# CompressorIface.net
KiCad netlist of a schematic drawn in Altium Designer
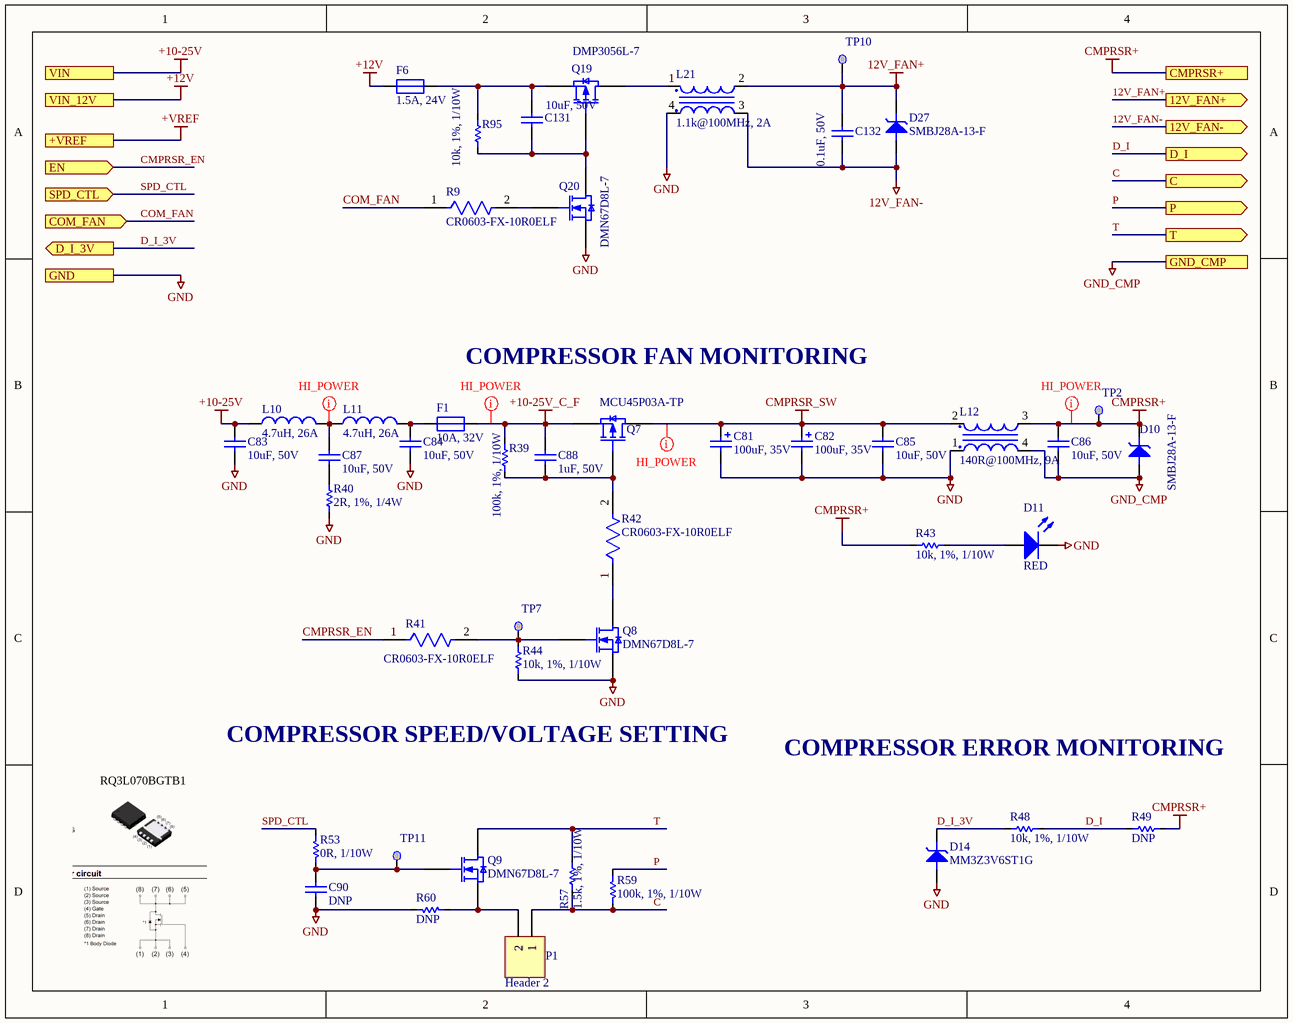
[diagram p0: CompressorIface.SchDoc]

(export (version "E")
  (design (tool "Eeschema 10.0.6"))
  (components
    (comp (ref "C81")
      (value "100uF, 35V")
      (footprint "CAPAE7866X80L")
      (description "CAP ALUM 100UF 20% 35V SMD")
      (fields (field (name "PART NUMBER") "NS00911"))
      (libsource (lib "FullPartsDB") (part "CAP_POL"))
    )
    (comp (ref "C82")
      (value "100uF, 35V")
      (footprint "CAPAE7866X80L")
      (description "CAP ALUM 100UF 20% 35V SMD")
      (fields (field (name "PART NUMBER") "NS00911"))
      (libsource (lib "FullPartsDB") (part "CAP_POL"))
    )
    (comp (ref "C83")
      (value "10uF, 50V")
      (footprint "1206")
      (description "CAP CER 10UF 50V X7R 1206")
      (fields (field (name "PART NUMBER") "NS00832"))
      (libsource (lib "FullPartsDB") (part "Cap"))
    )
    (comp (ref "C84")
      (value "10uF, 50V")
      (footprint "1206")
      (description "CAP CER 10UF 50V X7R 1206")
      (fields (field (name "PART NUMBER") "NS00832"))
      (libsource (lib "FullPartsDB") (part "Cap"))
    )
    (comp (ref "C85")
      (value "10uF, 50V")
      (footprint "1206")
      (description "CAP CER 10UF 50V X7R 1206")
      (fields (field (name "PART NUMBER") "NS00832"))
      (libsource (lib "FullPartsDB") (part "Cap"))
    )
    (comp (ref "C86")
      (value "10uF, 50V")
      (footprint "1206")
      (description "CAP CER 10UF 50V X7R 1206")
      (fields (field (name "PART NUMBER") "NS00832"))
      (libsource (lib "FullPartsDB") (part "Cap"))
    )
    (comp (ref "C87")
      (value "10uF, 50V")
      (footprint "1206")
      (description "CAP CER 10UF 50V X7R 1206")
      (fields (field (name "PART NUMBER") "NS00832"))
      (libsource (lib "FullPartsDB") (part "Cap"))
    )
    (comp (ref "C88")
      (value "1uF, 50V")
      (footprint "0805")
      (description "CAP CER 1UF 50V X7R 0805")
      (fields (field (name "PART NUMBER") "NS00871"))
      (libsource (lib "FullPartsDB") (part "Cap"))
    )
    (comp (ref "C90")
      (value "DNP")
      (footprint "0805")
      (description "0.10µF ±10% 50V Ceramic Capacitor X7R 0805 (2012 Metric)")
      (fields (field (name "PART NUMBER") "NS00353"))
      (libsource (lib "FullPartsDB") (part "Cap"))
    )
    (comp (ref "C131")
      (value "10uF, 50V")
      (footprint "1206")
      (description "CAP CER 10UF 50V X7R 1206")
      (fields (field (name "PART NUMBER") "NS00832"))
      (libsource (lib "FullPartsDB") (part "Cap"))
    )
    (comp (ref "C132")
      (value "0.1uF, 50V")
      (footprint "0603")
      (description "CAP CER 0.1UF 50V X7R 0603")
      (fields (field (name "PART NUMBER") "NS00838"))
      (libsource (lib "FullPartsDB") (part "Cap"))
    )
    (comp (ref "D10")
      (value "SMBJ28A-13-F")
      (footprint "SMB")
      (description "TVS DIODE 28VWM 45.4VC SMB")
      (fields (field (name "PART NUMBER") "NS00891"))
      (libsource (lib "FullPartsDB") (part "DiodeZener"))
    )
    (comp (ref "D11")
      (value "RED")
      (footprint "0603_DIODE_K1A2")
      (description "LED RED CLEAR 1608 SMD")
      (fields (field (name "PART NUMBER") "NS00945"))
      (libsource (lib "FullPartsDB") (part "LED_K1A2"))
    )
    (comp (ref "D14")
      (value "MM3Z3V6ST1G")
      (footprint "SOD323")
      (description "DIODE ZENER 3V 300MW SOD323")
      (fields (field (name "PART NUMBER") "NS00914"))
      (libsource (lib "FullPartsDB") (part "DiodeZener"))
    )
    (comp (ref "D27")
      (value "SMBJ28A-13-F")
      (footprint "SMB")
      (description "TVS DIODE 28VWM 45.4VC SMB")
      (fields (field (name "PART NUMBER") "NS00891"))
      (libsource (lib "FullPartsDB") (part "DiodeZener"))
    )
    (comp (ref "F1")
      (value "10A, 32V")
      (footprint "RAD_TH_1.3DIAx10.2Px27.9H")
      (description "PTC RESET FUSE 32V 10A RADIAL")
      (fields (field (name "PART NUMBER") "NS00921"))
      (libsource (lib "FullPartsDB") (part "Fuse"))
    )
    (comp (ref "F6")
      (value "1.5A, 24V")
      (footprint "1812_CAP")
      (description "PTC RESET FUSE 24V 1.5A 1812")
      (fields (field (name "PART NUMBER") "NS00950"))
      (libsource (lib "FullPartsDB") (part "Fuse"))
    )
    (comp (ref "L10")
      (value "4.7uH, 26A")
      (footprint "INDM178169X70N")
      (description "FIXED IND 4.7UH 26A 5.5 MOHM SMD")
      (fields (field (name "PART NUMBER") "NS00854"))
      (libsource (lib "FullPartsDB") (part "Inductor"))
    )
    (comp (ref "L11")
      (value "4.7uH, 26A")
      (footprint "INDM178169X70N")
      (description "FIXED IND 4.7UH 26A 5.5 MOHM SMD")
      (fields (field (name "PART NUMBER") "NS00854"))
      (libsource (lib "FullPartsDB") (part "Inductor"))
    )
    (comp (ref "L12")
      (value "140R@100MHz, 9A")
      (footprint "CHOKE_SMD_7.0X6.0X3.8")
      (description "CMC 1.8UH 9A 2LN 140 OHM SMD553-4125-1-ND")
      (fields (field (name "PART NUMBER") "NS00944"))
      (libsource (lib "FullPartsDB") (part "CHOKE_COMMON_ALT"))
    )
    (comp (ref "L21")
      (value "1.1k@100MHz, 2A")
      (footprint "PLCC440P435X370X235-4L")
      (description "CMC 2A 2LN 1.1K OHM SMD")
      (fields (field (name "PART NUMBER") "NS00952"))
      (libsource (lib "Schlib1") (part "CHOKE_COMMON_ALT"))
    )
    (comp (ref "P1")
      (value "Header 2")
      (footprint "HDR1X2")
      (description "Header, 2-Pin")
      (fields (field (name "PUBLISHER") "Altium Limited"))
      (libsource (lib "Miscellaneous Connectors") (part "Header 2"))
    )
    (comp (ref "Q7")
      (value "MCU45P03A-TP")
      (footprint "DPAK")
      (description "P-CHANNEL MOSFET, DPAK")
      (fields (field (name "PART NUMBER") "NS00810"))
      (libsource (lib "FullPartsDB") (part "FET_P_GDS"))
    )
    (comp (ref "Q8")
      (value "DMN67D8L-7")
      (footprint "SOT23-3")
      (description "MOSFET N-CH 60V 210MA SOT23")
      (fields (field (name "PART NUMBER") "NS00873") (field (name "PUBLISHER") "Altium Limited"))
      (libsource (lib "FullPartsDB") (part "FET_N_GSD"))
    )
    (comp (ref "Q9")
      (value "DMN67D8L-7")
      (footprint "SOT23-3")
      (description "MOSFET N-CH 60V 210MA SOT23")
      (fields (field (name "PART NUMBER") "NS00873") (field (name "PUBLISHER") "Altium Limited"))
      (libsource (lib "FullPartsDB") (part "FET_N_GSD"))
    )
    (comp (ref "Q19")
      (value "DMP3056L-7")
      (footprint "SOT23-3")
      (description "MOSFET P-CH 30V 4.3A SOT23")
      (fields (field (name "PART NUMBER") "NS00910"))
      (libsource (lib "FullPartsDB") (part "FET_P_GSD"))
    )
    (comp (ref "Q20")
      (value "DMN67D8L-7")
      (footprint "SOT23-3")
      (description "MOSFET N-CH 60V 210MA SOT23")
      (fields (field (name "PART NUMBER") "NS00873") (field (name "PUBLISHER") "Altium Limited"))
      (libsource (lib "FullPartsDB") (part "FET_N_GSD"))
    )
    (comp (ref "R9")
      (value "CR0603-FX-10R0ELF")
      (footprint "FP-CR0603-MFG")
      (description "Thick Film Chip Resistors 0603 10Ω 0.1W 1% 100ppm/°C")
      (fields (field (name "TOLERANCE") "1%"))
      (libsource (lib "Altium Content Vault") (part "1029c3af85768c4190bb7ad29bc67b5"))
    )
    (comp (ref "R39")
      (value "100k, 1%, 1/10W")
      (footprint "0603")
      (description "RES 100K OHM 1% 1/10W 0603")
      (fields (field (name "PART NUMBER") "NS00835"))
      (libsource (lib "FullPartsDB") (part "RESISTOR"))
    )
    (comp (ref "R40")
      (value "2R, 1%, 1/4W")
      (footprint "1206")
      (description "RES 2 OHM 1% 1/4W 1206")
      (fields (field (name "PART NUMBER") "NS00946"))
      (libsource (lib "FullPartsDB") (part "RESISTOR"))
    )
    (comp (ref "R41")
      (value "CR0603-FX-10R0ELF")
      (footprint "FP-CR0603-MFG")
      (description "Thick Film Chip Resistors 0603 10Ω 0.1W 1% 100ppm/°C")
      (fields (field (name "TOLERANCE") "1%"))
      (libsource (lib "Altium Content Vault") (part "1029c3af85768c4190bb7ad29bc67b5"))
    )
    (comp (ref "R42")
      (value "CR0603-FX-10R0ELF")
      (footprint "FP-CR0603-MFG")
      (description "Thick Film Chip Resistors 0603 10Ω 0.1W 1% 100ppm/°C")
      (fields (field (name "TOLERANCE") "1%"))
      (libsource (lib "Altium Content Vault") (part "1029c3af85768c4190bb7ad29bc67b5"))
    )
    (comp (ref "R43")
      (value "10k, 1%, 1/10W")
      (footprint "0603")
      (description "RES 10K OHM 1% 1/10W 0603")
      (fields (field (name "PART NUMBER") "NS00820"))
      (libsource (lib "FullPartsDB") (part "RESISTOR"))
    )
    (comp (ref "R44")
      (value "10k, 1%, 1/10W")
      (footprint "0603")
      (description "RES 10K OHM 1% 1/10W 0603")
      (fields (field (name "PART NUMBER") "NS00820"))
      (libsource (lib "FullPartsDB") (part "RESISTOR"))
    )
    (comp (ref "R48")
      (value "10k, 1%, 1/10W")
      (footprint "0603")
      (description "RES 10K OHM 1% 1/10W 0603")
      (fields (field (name "PART NUMBER") "NS00820"))
      (libsource (lib "FullPartsDB") (part "RESISTOR"))
    )
    (comp (ref "R49")
      (value "DNP")
      (footprint "0603")
      (description "RES 10K OHM 1% 1/10W 0603")
      (fields (field (name "PART NUMBER") "NS00820"))
      (libsource (lib "FullPartsDB") (part "RESISTOR"))
    )
    (comp (ref "R53")
      (value "0R, 1/10W")
      (footprint "0603")
      (description "RES 0 OHM JUMPER 1/10W 0603")
      (fields (field (name "PART NUMBER") "NS00876"))
      (libsource (lib "FullPartsDB") (part "RESISTOR"))
    )
    (comp (ref "R57")
      (value "1.5k, 1%, 1/10W")
      (footprint "0603")
      (description "RES 1.5K OHM 1% 1/10W 0603")
      (fields (field (name "PART NUMBER") "NS00951"))
      (libsource (lib "FullPartsDB") (part "RESISTOR"))
    )
    (comp (ref "R59")
      (value "100k, 1%, 1/10W")
      (footprint "0603")
      (description "RES SMD 100K OHM 1% 1/10W 0603")
      (fields (field (name "PART NUMBER") "NS00915"))
      (libsource (lib "FullPartsDB") (part "RESISTOR"))
    )
    (comp (ref "R60")
      (value "DNP")
      (footprint "0603")
      (description "RES 300kOHM JUMPER 1/10W 0603")
      (fields (field (name "PART NUMBER") "NS00876"))
      (libsource (lib "FullPartsDB") (part "RESISTOR"))
    )
    (comp (ref "R95")
      (value "10k, 1%, 1/10W")
      (footprint "0603")
      (description "RES 10K OHM 1% 1/10W 0603")
      (fields (field (name "PART NUMBER") "NS00820"))
      (libsource (lib "FullPartsDB") (part "RESISTOR"))
    )
    (comp (ref "TP2")
      (value "Test Point")
      (footprint "TEST POINT 40 Mil")
      (description "Test Point 0.3mm")
      (libsource (lib "1_EverythingElse") (part "Test Point"))
    )
    (comp (ref "TP7")
      (value "Test Point")
      (footprint "TEST POINT 40 Mil")
      (description "Test Point 0.3mm")
      (libsource (lib "1_EverythingElse") (part "Test Point"))
    )
    (comp (ref "TP10")
      (value "Test Point")
      (footprint "TEST POINT 40 Mil")
      (description "Test Point 0.3mm")
      (libsource (lib "1_EverythingElse") (part "Test Point"))
    )
    (comp (ref "TP11")
      (value "Test Point")
      (footprint "TEST POINT 40 Mil")
      (description "Test Point 0.3mm")
      (libsource (lib "1_EverythingElse") (part "Test Point"))
    )
  )
  (nets
    (net (code "1") (name "+10-25V") (class "Default")
      (node (ref "C83") (pin "2") (pinfunction "2_2") (pintype "passive"))
      (node (ref "L10") (pin "1") (pinfunction "1_1") (pintype "passive"))
    )
    (net (code "2") (name "+10-25V_C_F") (class "Default")
      (node (ref "C88") (pin "2") (pinfunction "2_2") (pintype "passive"))
      (node (ref "F1") (pin "1") (pinfunction "A_1") (pintype "passive"))
      (node (ref "Q7") (pin "3") (pinfunction "S_3") (pintype "passive"))
      (node (ref "R39") (pin "2") (pinfunction "2_2") (pintype "passive"))
    )
    (net (code "3") (name "+12V") (class "Default")
      (node (ref "F6") (pin "2") (pinfunction "K_2") (pintype "passive"))
    )
    (net (code "5") (name "/C") (class "Default")
      (node (ref "P1") (pin "1") (pinfunction "1_1") (pintype "passive"))
      (node (ref "R57") (pin "1") (pinfunction "1_1") (pintype "passive"))
      (node (ref "R59") (pin "2") (pinfunction "2_2") (pintype "passive"))
    )
    (net (code "6") (name "/CMPRSR_EN") (class "Default")
      (node (ref "R41") (pin "1") (pinfunction "1_1") (pintype "passive"))
    )
    (net (code "7") (name "/COM_FAN") (class "Default")
      (node (ref "R9") (pin "1") (pinfunction "1_1") (pintype "passive"))
    )
    (net (code "8") (name "/D_I") (class "Default")
      (node (ref "R48") (pin "1") (pinfunction "1_1") (pintype "passive"))
      (node (ref "R49") (pin "2") (pinfunction "2_2") (pintype "passive"))
    )
    (net (code "9") (name "/D_I_3V") (class "Default")
      (node (ref "D14") (pin "2") (pinfunction "K_2") (pintype "passive"))
      (node (ref "R48") (pin "2") (pinfunction "2_2") (pintype "passive"))
    )
    (net (code "10") (name "/P") (class "Default")
      (node (ref "R59") (pin "1") (pinfunction "1_1") (pintype "passive"))
    )
    (net (code "11") (name "/SPD_CTL") (class "Default")
      (node (ref "R53") (pin "1") (pinfunction "1_1") (pintype "passive"))
    )
    (net (code "12") (name "/T") (class "Default")
      (node (ref "Q9") (pin "3") (pinfunction "D_3") (pintype "passive"))
      (node (ref "R57") (pin "2") (pinfunction "2_2") (pintype "passive"))
    )
    (net (code "13") (name "12V_FAN+") (class "Default")
      (node (ref "C132") (pin "2") (pinfunction "2_2") (pintype "passive"))
      (node (ref "D27") (pin "2") (pinfunction "K_2") (pintype "passive"))
      (node (ref "L21") (pin "2") (pinfunction "2_2") (pintype "passive"))
      (node (ref "TP10") (pin "1") (pinfunction "1_1") (pintype "passive"))
    )
    (net (code "14") (name "12V_FAN-") (class "Default")
      (node (ref "C132") (pin "1") (pinfunction "1_1") (pintype "passive"))
      (node (ref "D27") (pin "1") (pinfunction "A_1") (pintype "passive"))
      (node (ref "L21") (pin "3") (pinfunction "3_3") (pintype "passive"))
    )
    (net (code "15") (name "CMPRSR+") (class "Default")
      (node (ref "C86") (pin "2") (pinfunction "2_2") (pintype "passive"))
      (node (ref "D10") (pin "2") (pinfunction "K_2") (pintype "passive"))
      (node (ref "L12") (pin "3") (pinfunction "3_3") (pintype "passive"))
      (node (ref "R43") (pin "2") (pinfunction "2_2") (pintype "passive"))
      (node (ref "R49") (pin "1") (pinfunction "1_1") (pintype "passive"))
      (node (ref "TP2") (pin "1") (pinfunction "1_1") (pintype "passive"))
    )
    (net (code "16") (name "CMPRSR_SW") (class "Default")
      (node (ref "C81") (pin "1") (pinfunction "1_1") (pintype "passive"))
      (node (ref "C82") (pin "1") (pinfunction "1_1") (pintype "passive"))
      (node (ref "C85") (pin "2") (pinfunction "2_2") (pintype "passive"))
      (node (ref "L12") (pin "2") (pinfunction "2_2") (pintype "passive"))
      (node (ref "Q7") (pin "2") (pinfunction "D_2") (pintype "passive"))
    )
    (net (code "17") (name "GND") (class "Default")
      (node (ref "C81") (pin "2") (pinfunction "2_2") (pintype "passive"))
      (node (ref "C82") (pin "2") (pinfunction "2_2") (pintype "passive"))
      (node (ref "C83") (pin "1") (pinfunction "1_1") (pintype "passive"))
      (node (ref "C84") (pin "1") (pinfunction "1_1") (pintype "passive"))
      (node (ref "C85") (pin "1") (pinfunction "1_1") (pintype "passive"))
      (node (ref "C90") (pin "1") (pinfunction "1_1") (pintype "passive"))
      (node (ref "D11") (pin "2") (pinfunction "K_2") (pintype "passive"))
      (node (ref "D14") (pin "1") (pinfunction "A_1") (pintype "passive"))
      (node (ref "L12") (pin "1") (pinfunction "1_1") (pintype "passive"))
      (node (ref "L21") (pin "4") (pinfunction "4_4") (pintype "passive"))
      (node (ref "Q20") (pin "2") (pinfunction "S_2") (pintype "passive"))
      (node (ref "Q8") (pin "2") (pinfunction "S_2") (pintype "passive"))
      (node (ref "R40") (pin "1") (pinfunction "1_1") (pintype "passive"))
      (node (ref "R44") (pin "1") (pinfunction "1_1") (pintype "passive"))
      (node (ref "R60") (pin "1") (pinfunction "1_1") (pintype "passive"))
    )
    (net (code "18") (name "GND_CMP") (class "Default")
      (node (ref "C86") (pin "1") (pinfunction "1_1") (pintype "passive"))
      (node (ref "D10") (pin "1") (pinfunction "A_1") (pintype "passive"))
      (node (ref "L12") (pin "4") (pinfunction "4_4") (pintype "passive"))
    )
    (net (code "19") (name "Net-(C87-Pad1)") (class "Default")
      (node (ref "C87") (pin "1") (pinfunction "1_1") (pintype "passive"))
      (node (ref "R40") (pin "2") (pinfunction "2_2") (pintype "passive"))
    )
    (net (code "20") (name "Net-(C87-Pad2)") (class "Default")
      (node (ref "C87") (pin "2") (pinfunction "2_2") (pintype "passive"))
      (node (ref "L10") (pin "2") (pinfunction "2_2") (pintype "passive"))
      (node (ref "L11") (pin "1") (pinfunction "1_1") (pintype "passive"))
    )
    (net (code "21") (name "Net-(D11-A)") (class "Default")
      (node (ref "D11") (pin "1") (pinfunction "A_1") (pintype "passive"))
      (node (ref "R43") (pin "1") (pinfunction "1_1") (pintype "passive"))
    )
    (net (code "22") (name "Net-(F1-K)") (class "Default")
      (node (ref "C84") (pin "2") (pinfunction "2_2") (pintype "passive"))
      (node (ref "F1") (pin "2") (pinfunction "K_2") (pintype "passive"))
      (node (ref "L11") (pin "2") (pinfunction "2_2") (pintype "passive"))
    )
    (net (code "23") (name "Net-(F6-A)") (class "Default")
      (node (ref "C131") (pin "1") (pinfunction "1_1") (pintype "passive"))
      (node (ref "F6") (pin "1") (pinfunction "A_1") (pintype "passive"))
      (node (ref "Q19") (pin "2") (pinfunction "S_2") (pintype "passive"))
      (node (ref "R95") (pin "1") (pinfunction "1_1") (pintype "passive"))
    )
    (net (code "24") (name "Net-(Q7-G)") (class "Default")
      (node (ref "C88") (pin "1") (pinfunction "1_1") (pintype "passive"))
      (node (ref "Q7") (pin "1") (pinfunction "G_1") (pintype "passive"))
      (node (ref "R39") (pin "1") (pinfunction "1_1") (pintype "passive"))
      (node (ref "R42") (pin "2") (pinfunction "2_2") (pintype "passive"))
    )
    (net (code "25") (name "Net-(Q8-D)") (class "Default")
      (node (ref "Q8") (pin "3") (pinfunction "D_3") (pintype "passive"))
      (node (ref "R42") (pin "1") (pinfunction "1_1") (pintype "passive"))
    )
    (net (code "26") (name "Net-(Q8-G)") (class "Default")
      (node (ref "Q8") (pin "1") (pinfunction "G_1") (pintype "passive"))
      (node (ref "R41") (pin "2") (pinfunction "2_2") (pintype "passive"))
      (node (ref "R44") (pin "2") (pinfunction "2_2") (pintype "passive"))
      (node (ref "TP7") (pin "1") (pinfunction "1_1") (pintype "passive"))
    )
    (net (code "27") (name "Net-(Q9-G)") (class "Default")
      (node (ref "C90") (pin "2") (pinfunction "2_2") (pintype "passive"))
      (node (ref "Q9") (pin "1") (pinfunction "G_1") (pintype "passive"))
      (node (ref "R53") (pin "2") (pinfunction "2_2") (pintype "passive"))
      (node (ref "TP11") (pin "1") (pinfunction "1_1") (pintype "passive"))
    )
    (net (code "28") (name "Net-(Q9-S)") (class "Default")
      (node (ref "P1") (pin "2") (pinfunction "2_2") (pintype "passive"))
      (node (ref "Q9") (pin "2") (pinfunction "S_2") (pintype "passive"))
      (node (ref "R60") (pin "2") (pinfunction "2_2") (pintype "passive"))
    )
    (net (code "29") (name "Net-(Q19-D)") (class "Default")
      (node (ref "L21") (pin "1") (pinfunction "1_1") (pintype "passive"))
      (node (ref "Q19") (pin "3") (pinfunction "D_3") (pintype "passive"))
    )
    (net (code "30") (name "Net-(Q19-G)") (class "Default")
      (node (ref "C131") (pin "2") (pinfunction "2_2") (pintype "passive"))
      (node (ref "Q19") (pin "1") (pinfunction "G_1") (pintype "passive"))
      (node (ref "Q20") (pin "3") (pinfunction "D_3") (pintype "passive"))
      (node (ref "R95") (pin "2") (pinfunction "2_2") (pintype "passive"))
    )
    (net (code "31") (name "Net-(Q20-G)") (class "Default")
      (node (ref "Q20") (pin "1") (pinfunction "G_1") (pintype "passive"))
      (node (ref "R9") (pin "2") (pinfunction "2_2") (pintype "passive"))
    )
  )
)
